# mainboard_motor_v1_2.net
KiCad netlist of a schematic drawn in Altium Designer
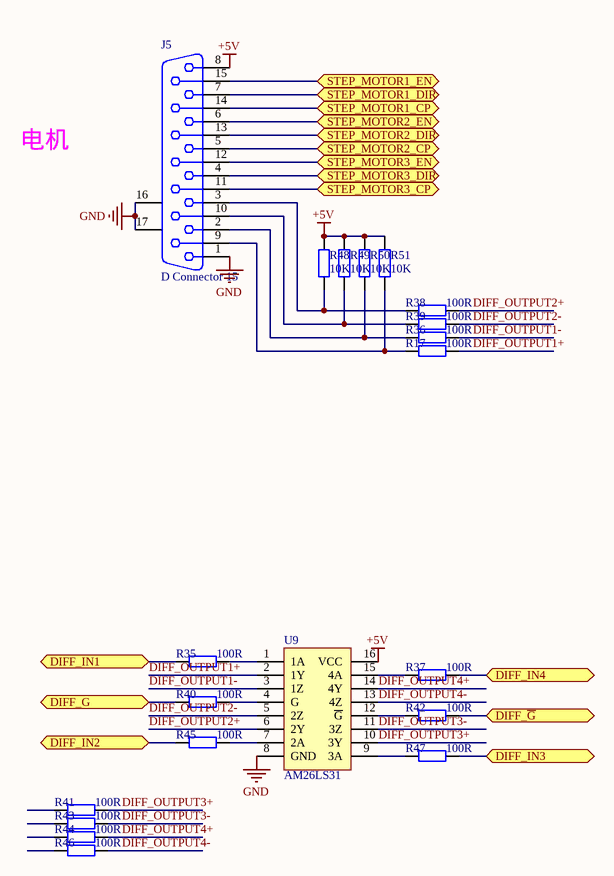
[diagram p0: mainboard_motor.v1.2.SchDoc]

(export (version "E")
  (design (tool "Eeschema 10.0.6"))
  (components
    (comp (ref "J5")
      (value "D Connector 15")
      (footprint "DSUB1.385-2H15")
      (description "Receptacle Assembly, 15 Position, Right Angle")
      (fields (field (name "PUBLISHER") "Altium Limited"))
      (libsource (lib "Miscellaneous Connectors") (part "D Connector 15"))
    )
    (comp (ref "R17")
      (value "100R")
      (footprint "0805")
      (description "Resistor")
      (fields (field (name "PUBLISHER") "Altium Limited"))
      (libsource (lib "") (part "Res2_1"))
    )
    (comp (ref "R35")
      (value "100R")
      (footprint "0805")
      (description "Resistor")
      (fields (field (name "PUBLISHER") "Altium Limited"))
      (libsource (lib "") (part "Res2_1"))
    )
    (comp (ref "R36")
      (value "100R")
      (footprint "0805")
      (description "Resistor")
      (fields (field (name "PUBLISHER") "Altium Limited"))
      (libsource (lib "") (part "Res2_1"))
    )
    (comp (ref "R37")
      (value "100R")
      (footprint "0805")
      (description "Resistor")
      (fields (field (name "PUBLISHER") "Altium Limited"))
      (libsource (lib "") (part "Res2_1"))
    )
    (comp (ref "R38")
      (value "100R")
      (footprint "0805")
      (description "Resistor")
      (fields (field (name "PUBLISHER") "Altium Limited"))
      (libsource (lib "") (part "Res2_1"))
    )
    (comp (ref "R39")
      (value "100R")
      (footprint "0805")
      (description "Resistor")
      (fields (field (name "PUBLISHER") "Altium Limited"))
      (libsource (lib "") (part "Res2_1"))
    )
    (comp (ref "R40")
      (value "100R")
      (footprint "0805")
      (description "Resistor")
      (fields (field (name "PUBLISHER") "Altium Limited"))
      (libsource (lib "") (part "Res2_1"))
    )
    (comp (ref "R41")
      (value "100R")
      (footprint "0805")
      (description "Resistor")
      (fields (field (name "PUBLISHER") "Altium Limited"))
      (libsource (lib "") (part "Res2_1"))
    )
    (comp (ref "R42")
      (value "100R")
      (footprint "0805")
      (description "Resistor")
      (fields (field (name "PUBLISHER") "Altium Limited"))
      (libsource (lib "") (part "Res2_1"))
    )
    (comp (ref "R43")
      (value "100R")
      (footprint "0805")
      (description "Resistor")
      (fields (field (name "PUBLISHER") "Altium Limited"))
      (libsource (lib "") (part "Res2_1"))
    )
    (comp (ref "R44")
      (value "100R")
      (footprint "0805")
      (description "Resistor")
      (fields (field (name "PUBLISHER") "Altium Limited"))
      (libsource (lib "") (part "Res2_1"))
    )
    (comp (ref "R45")
      (value "100R")
      (footprint "0805")
      (description "Resistor")
      (fields (field (name "PUBLISHER") "Altium Limited"))
      (libsource (lib "") (part "Res2_1"))
    )
    (comp (ref "R46")
      (value "100R")
      (footprint "0805")
      (description "Resistor")
      (fields (field (name "PUBLISHER") "Altium Limited"))
      (libsource (lib "") (part "Res2_1"))
    )
    (comp (ref "R47")
      (value "100R")
      (footprint "0805")
      (description "Resistor")
      (fields (field (name "PUBLISHER") "Altium Limited"))
      (libsource (lib "") (part "Res2_1"))
    )
    (comp (ref "R48")
      (value "10K")
      (footprint "0805")
      (description "Resistor")
      (fields (field (name "PUBLISHER") "Altium Limited"))
      (libsource (lib "TIAN's Schlib") (part "Res2"))
    )
    (comp (ref "R49")
      (value "10K")
      (footprint "0805")
      (description "Resistor")
      (fields (field (name "PUBLISHER") "Altium Limited"))
      (libsource (lib "TIAN's Schlib") (part "Res2"))
    )
    (comp (ref "R50")
      (value "10K")
      (footprint "0805")
      (description "Resistor")
      (fields (field (name "PUBLISHER") "Altium Limited"))
      (libsource (lib "TIAN's Schlib") (part "Res2"))
    )
    (comp (ref "R51")
      (value "10K")
      (footprint "0805")
      (description "Resistor")
      (fields (field (name "PUBLISHER") "Altium Limited"))
      (libsource (lib "TIAN's Schlib") (part "Res2"))
    )
    (comp (ref "U9") (value "AM26LS31") (footprint "SO-16") (libsource (lib "Chip") (part "AM26LS31")))
  )
  (nets
    (net (code "1") (name "+5V") (class "Default")
      (node (ref "J5") (pin "8") (pinfunction "8_8") (pintype "passive"))
      (node (ref "R48") (pin "1") (pinfunction "1_1") (pintype "passive"))
      (node (ref "R49") (pin "1") (pinfunction "1_1") (pintype "passive"))
      (node (ref "R50") (pin "1") (pinfunction "1_1") (pintype "passive"))
      (node (ref "R51") (pin "1") (pinfunction "1_1") (pintype "passive"))
      (node (ref "U9") (pin "16") (pinfunction "VCC_16") (pintype "passive"))
    )
    (net (code "2") (name "/DIFF_G") (class "Default")
      (node (ref "R40") (pin "2") (pinfunction "2_2") (pintype "passive"))
    )
    (net (code "3") (name "/DIFF_IN1") (class "Default")
      (node (ref "R35") (pin "2") (pinfunction "2_2") (pintype "passive"))
    )
    (net (code "4") (name "/DIFF_IN2") (class "Default")
      (node (ref "R45") (pin "2") (pinfunction "2_2") (pintype "passive"))
    )
    (net (code "5") (name "/DIFF_IN3") (class "Default")
      (node (ref "R47") (pin "1") (pinfunction "1_1") (pintype "passive"))
    )
    (net (code "6") (name "/DIFF_IN4") (class "Default")
      (node (ref "R37") (pin "1") (pinfunction "1_1") (pintype "passive"))
    )
    (net (code "7") (name "/DIFF_OUTPUT1+") (class "Default")
      (node (ref "R17") (pin "1") (pinfunction "1_1") (pintype "passive"))
      (node (ref "U9") (pin "2") (pinfunction "1Y_2") (pintype "passive"))
    )
    (net (code "8") (name "/DIFF_OUTPUT1-") (class "Default")
      (node (ref "R36") (pin "1") (pinfunction "1_1") (pintype "passive"))
      (node (ref "U9") (pin "3") (pinfunction "1Z_3") (pintype "passive"))
    )
    (net (code "9") (name "/DIFF_OUTPUT2+") (class "Default")
      (node (ref "R38") (pin "1") (pinfunction "1_1") (pintype "passive"))
      (node (ref "U9") (pin "6") (pinfunction "2Y_6") (pintype "passive"))
    )
    (net (code "10") (name "/DIFF_OUTPUT2-") (class "Default")
      (node (ref "R39") (pin "1") (pinfunction "1_1") (pintype "passive"))
      (node (ref "U9") (pin "5") (pinfunction "2Z_5") (pintype "passive"))
    )
    (net (code "11") (name "/DIFF_OUTPUT3+") (class "Default")
      (node (ref "R41") (pin "1") (pinfunction "1_1") (pintype "passive"))
      (node (ref "U9") (pin "10") (pinfunction "3Y_10") (pintype "passive"))
    )
    (net (code "12") (name "/DIFF_OUTPUT3-") (class "Default")
      (node (ref "R43") (pin "1") (pinfunction "1_1") (pintype "passive"))
      (node (ref "U9") (pin "11") (pinfunction "3Z_11") (pintype "passive"))
    )
    (net (code "13") (name "/DIFF_OUTPUT4+") (class "Default")
      (node (ref "R44") (pin "1") (pinfunction "1_1") (pintype "passive"))
      (node (ref "U9") (pin "14") (pinfunction "4Y_14") (pintype "passive"))
    )
    (net (code "14") (name "/DIFF_OUTPUT4-") (class "Default")
      (node (ref "R46") (pin "1") (pinfunction "1_1") (pintype "passive"))
      (node (ref "U9") (pin "13") (pinfunction "4Z_13") (pintype "passive"))
    )
    (net (code "15") (name "/DIFF_~{G}") (class "Default")
      (node (ref "R42") (pin "1") (pinfunction "1_1") (pintype "passive"))
    )
    (net (code "16") (name "/STEP_MOTOR1_CP") (class "Default")
      (node (ref "J5") (pin "14") (pinfunction "14_14") (pintype "passive"))
    )
    (net (code "17") (name "/STEP_MOTOR1_DIR") (class "Default")
      (node (ref "J5") (pin "7") (pinfunction "7_7") (pintype "passive"))
    )
    (net (code "18") (name "/STEP_MOTOR1_EN") (class "Default")
      (node (ref "J5") (pin "15") (pinfunction "15_15") (pintype "passive"))
    )
    (net (code "19") (name "/STEP_MOTOR2_CP") (class "Default")
      (node (ref "J5") (pin "5") (pinfunction "5_5") (pintype "passive"))
    )
    (net (code "20") (name "/STEP_MOTOR2_DIR") (class "Default")
      (node (ref "J5") (pin "13") (pinfunction "13_13") (pintype "passive"))
    )
    (net (code "21") (name "/STEP_MOTOR2_EN") (class "Default")
      (node (ref "J5") (pin "6") (pinfunction "6_6") (pintype "passive"))
    )
    (net (code "22") (name "/STEP_MOTOR3_CP") (class "Default")
      (node (ref "J5") (pin "11") (pinfunction "11_11") (pintype "passive"))
    )
    (net (code "23") (name "/STEP_MOTOR3_DIR") (class "Default")
      (node (ref "J5") (pin "4") (pinfunction "4_4") (pintype "passive"))
    )
    (net (code "24") (name "/STEP_MOTOR3_EN") (class "Default")
      (node (ref "J5") (pin "12") (pinfunction "12_12") (pintype "passive"))
    )
    (net (code "25") (name "GND") (class "Default")
      (node (ref "J5") (pin "1") (pinfunction "1_1") (pintype "passive"))
      (node (ref "J5") (pin "16") (pinfunction "MH1_16") (pintype "passive"))
      (node (ref "J5") (pin "17") (pinfunction "MH2_17") (pintype "passive"))
      (node (ref "U9") (pin "8") (pinfunction "GND_8") (pintype "passive"))
    )
    (net (code "26") (name "Net-(J5-Pad2)") (class "Default")
      (node (ref "J5") (pin "2") (pinfunction "2_2") (pintype "passive"))
      (node (ref "R36") (pin "2") (pinfunction "2_2") (pintype "passive"))
      (node (ref "R50") (pin "2") (pinfunction "2_2") (pintype "passive"))
    )
    (net (code "27") (name "Net-(J5-Pad3)") (class "Default")
      (node (ref "J5") (pin "3") (pinfunction "3_3") (pintype "passive"))
      (node (ref "R38") (pin "2") (pinfunction "2_2") (pintype "passive"))
      (node (ref "R48") (pin "2") (pinfunction "2_2") (pintype "passive"))
    )
    (net (code "28") (name "Net-(J5-Pad9)") (class "Default")
      (node (ref "J5") (pin "9") (pinfunction "9_9") (pintype "passive"))
      (node (ref "R17") (pin "2") (pinfunction "2_2") (pintype "passive"))
      (node (ref "R51") (pin "2") (pinfunction "2_2") (pintype "passive"))
    )
    (net (code "29") (name "Net-(J5-Pad10)") (class "Default")
      (node (ref "J5") (pin "10") (pinfunction "10_10") (pintype "passive"))
      (node (ref "R39") (pin "2") (pinfunction "2_2") (pintype "passive"))
      (node (ref "R49") (pin "2") (pinfunction "2_2") (pintype "passive"))
    )
    (net (code "30") (name "Net-(U9-1A)") (class "Default")
      (node (ref "R35") (pin "1") (pinfunction "1_1") (pintype "passive"))
      (node (ref "U9") (pin "1") (pinfunction "1A_1") (pintype "passive"))
    )
    (net (code "31") (name "Net-(U9-2A)") (class "Default")
      (node (ref "R45") (pin "1") (pinfunction "1_1") (pintype "passive"))
      (node (ref "U9") (pin "7") (pinfunction "2A_7") (pintype "passive"))
    )
    (net (code "32") (name "Net-(U9-3A)") (class "Default")
      (node (ref "R47") (pin "2") (pinfunction "2_2") (pintype "passive"))
      (node (ref "U9") (pin "9") (pinfunction "3A_9") (pintype "passive"))
    )
    (net (code "33") (name "Net-(U9-4A)") (class "Default")
      (node (ref "R37") (pin "2") (pinfunction "2_2") (pintype "passive"))
      (node (ref "U9") (pin "15") (pinfunction "4A_15") (pintype "passive"))
    )
    (net (code "34") (name "Net-(U9-G)") (class "Default")
      (node (ref "R40") (pin "1") (pinfunction "1_1") (pintype "passive"))
      (node (ref "U9") (pin "4") (pinfunction "G_4") (pintype "passive"))
    )
    (net (code "35") (name "Net-(U9-~{G})") (class "Default")
      (node (ref "R42") (pin "2") (pinfunction "2_2") (pintype "passive"))
      (node (ref "U9") (pin "12") (pinfunction "~{G}_12") (pintype "passive"))
    )
    (net (code "36") (name "unconnected-(R41-Pad2)") (class "Default")
      (node (ref "R41") (pin "2") (pinfunction "2_2") (pintype "passive"))
    )
    (net (code "37") (name "unconnected-(R43-Pad2)") (class "Default")
      (node (ref "R43") (pin "2") (pinfunction "2_2") (pintype "passive"))
    )
    (net (code "38") (name "unconnected-(R44-Pad2)") (class "Default")
      (node (ref "R44") (pin "2") (pinfunction "2_2") (pintype "passive"))
    )
    (net (code "39") (name "unconnected-(R46-Pad2)") (class "Default")
      (node (ref "R46") (pin "2") (pinfunction "2_2") (pintype "passive"))
    )
  )
)
